# LDAQ-MOD-ENC4.net
KiCad netlist of a schematic drawn in EAGLE
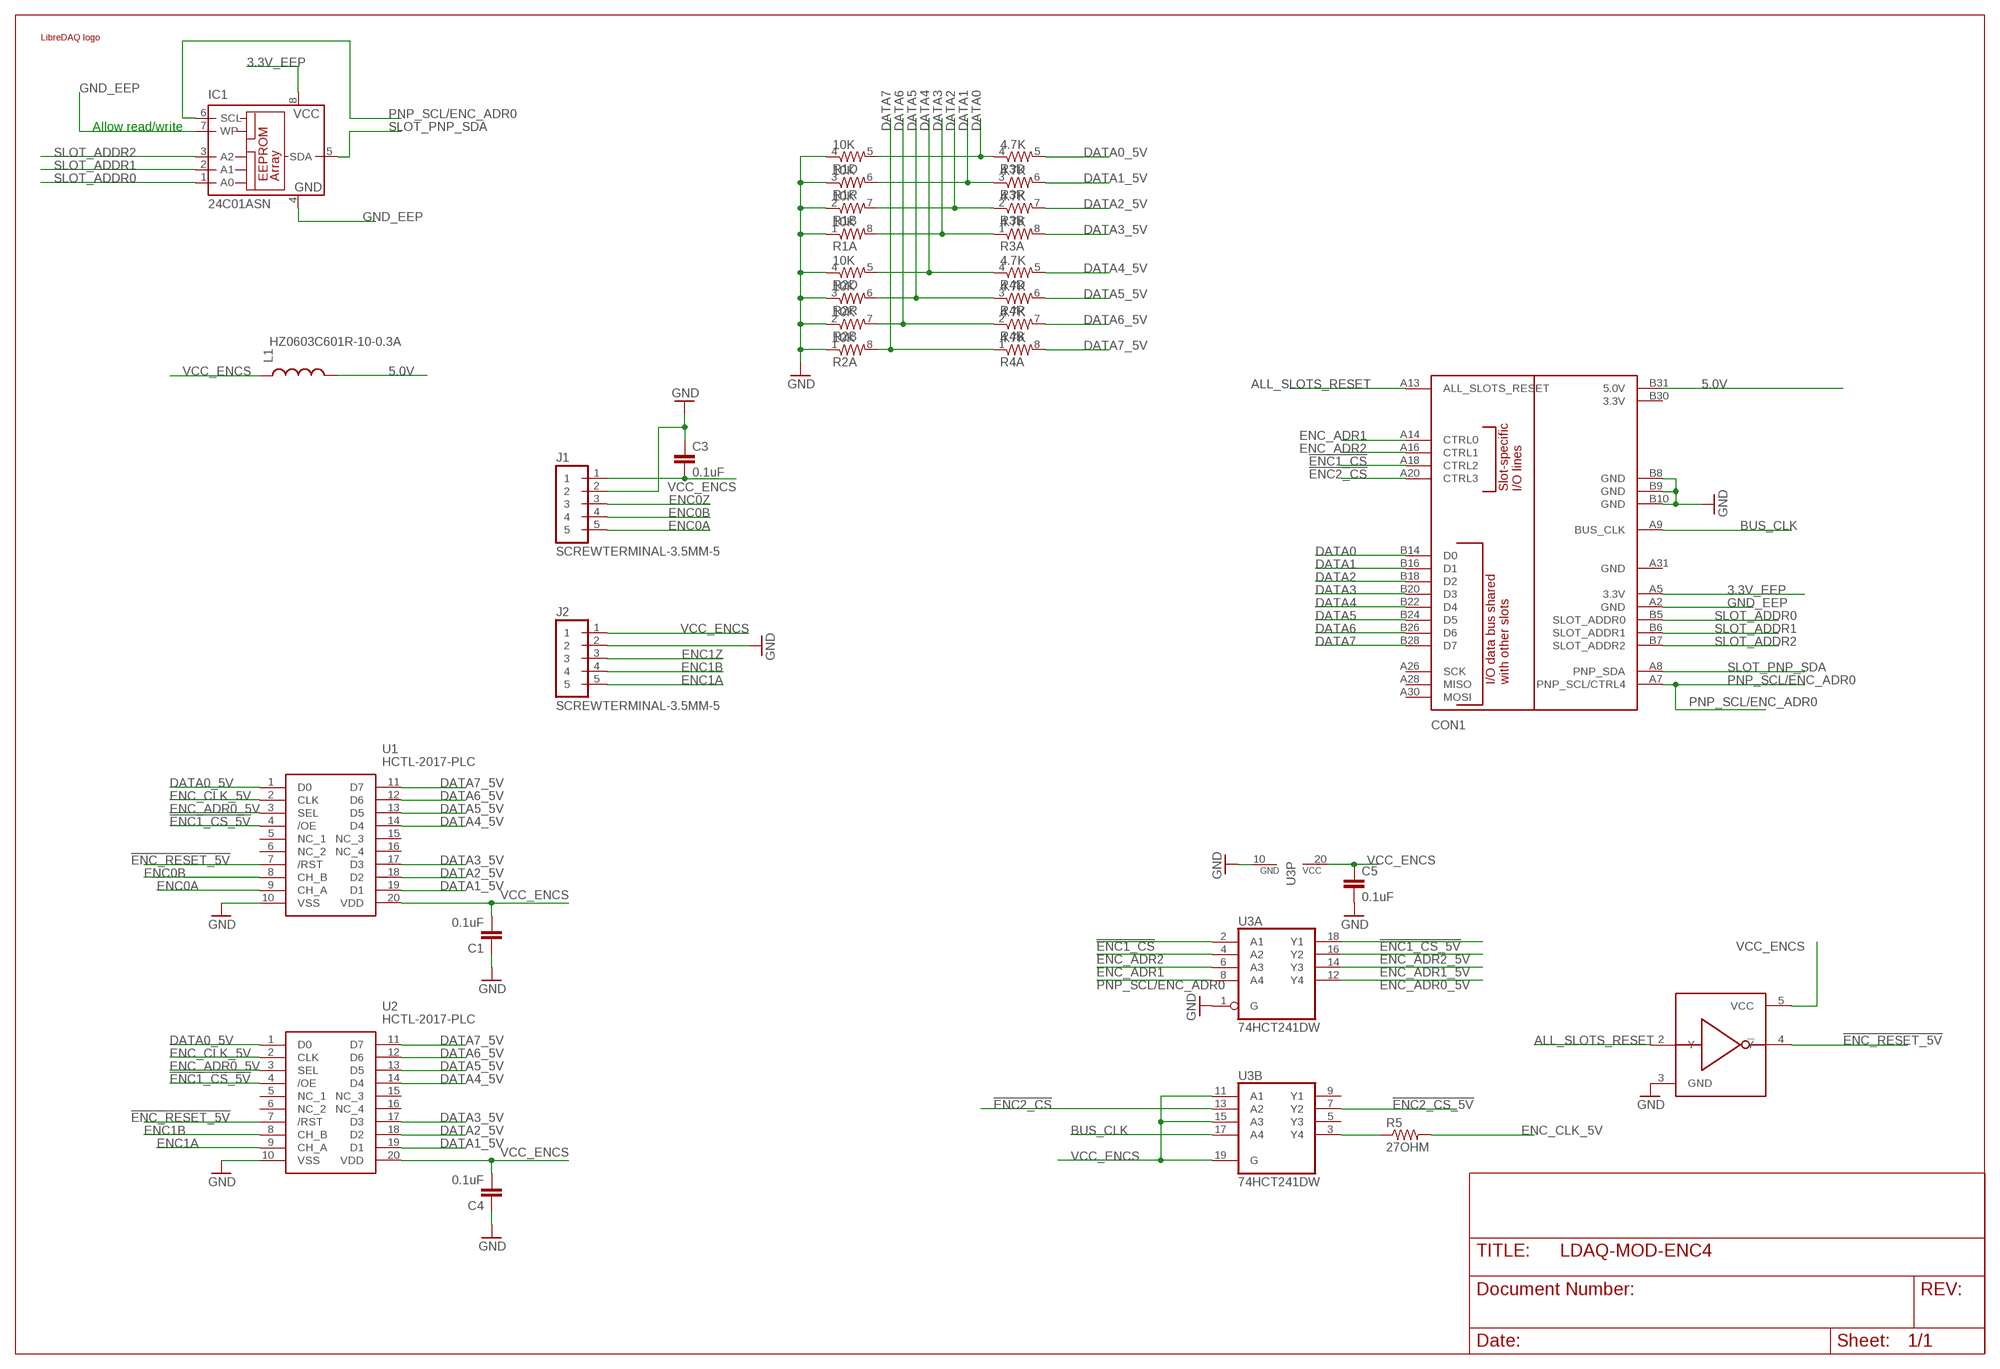
[diagram p0: schematic, sheet 1]

(export (version "E")
  (design (tool "Eeschema 10.0.6"))
  (components
    (comp (ref "C1")
      (value "0.1uF")
      (footprint "eagle-import:0603-CAP")
      (libsource (lib "eagle-import") (part "0.1UF-25V(+80/-20%)(0603)"))
    )
    (comp (ref "C3")
      (value "0.1uF")
      (footprint "eagle-import:0603-CAP")
      (libsource (lib "eagle-import") (part "0.1UF-25V(+80/-20%)(0603)"))
    )
    (comp (ref "C4")
      (value "0.1uF")
      (footprint "eagle-import:0603-CAP")
      (libsource (lib "eagle-import") (part "0.1UF-25V(+80/-20%)(0603)"))
    )
    (comp (ref "C5")
      (value "0.1uF")
      (footprint "eagle-import:0603-CAP")
      (libsource (lib "eagle-import") (part "0.1UF-25V(+80/-20%)(0603)"))
    )
    (comp (ref "CON1")
      (value "BOARD")
      (footprint "eagle-import:PCI-E_64_EDGE_70X60_PADS-ONLY")
      (libsource (lib "eagle-import") (part "LIBREDAQ_DAUGHTER_BOARDPCI-64-SIZE1-PADS"))
    )
    (comp (ref "IC1")
      (value "24C01ASN")
      (footprint "eagle-import:SO-08")
      (fields (field (name "MPN") "AT24C01BN-SH-B"))
      (libsource (lib "eagle-import") (part "24CSN01A"))
    )
    (comp (ref "J1")
      (value "SCREWTERMINAL-3.5MM-5")
      (footprint "eagle-import:SCREWTERMINAL-3.5MM-5")
      (libsource (lib "eagle-import") (part "SCREWTERMINAL-3.5MM-5"))
    )
    (comp (ref "J2")
      (value "SCREWTERMINAL-3.5MM-5")
      (footprint "eagle-import:SCREWTERMINAL-3.5MM-5")
      (libsource (lib "eagle-import") (part "SCREWTERMINAL-3.5MM-5"))
    )
    (comp (ref "L1")
      (value "HZ0603C601R-10-0.3A")
      (footprint "eagle-import:0603")
      (libsource (lib "eagle-import") (part "INDUCTOR0603"))
    )
    (comp (ref "LOGO1")
      (value "LIBREDAQ_LOGO_MINILOGO_GENERIC")
      (footprint "eagle-import:LIBREDAQ_LOGO")
      (libsource (lib "eagle-import") (part "LIBREDAQ_LOGO_MINILOGO_GENERIC"))
    )
    (comp (ref "R1")
      (value "10K")
      (footprint "eagle-import:0603-ARV")
      (libsource (lib "eagle-import") (part "RESISTOR-ARRAY0603-ARV"))
    )
    (comp (ref "R2")
      (value "10K")
      (footprint "eagle-import:0603-ARV")
      (libsource (lib "eagle-import") (part "RESISTOR-ARRAY0603-ARV"))
    )
    (comp (ref "R3")
      (value "4.7K")
      (footprint "eagle-import:0603-ARV")
      (libsource (lib "eagle-import") (part "RESISTOR-ARRAY0603-ARV"))
    )
    (comp (ref "R4")
      (value "4.7K")
      (footprint "eagle-import:0603-ARV")
      (libsource (lib "eagle-import") (part "RESISTOR-ARRAY0603-ARV"))
    )
    (comp (ref "R5")
      (value "27OHM")
      (footprint "eagle-import:0603")
      (libsource (lib "eagle-import") (part "33OHM1/10W1%(0603)"))
    )
    (comp (ref "U1")
      (value "HCTL-2017-PLC")
      (footprint "eagle-import:PLCC127P991X991X457-20N")
      (libsource (lib "eagle-import") (part "HCTL-2017-PLC"))
    )
    (comp (ref "U2")
      (value "HCTL-2017-PLC")
      (footprint "eagle-import:PLCC127P991X991X457-20N")
      (libsource (lib "eagle-import") (part "HCTL-2017-PLC"))
    )
    (comp (ref "U3")
      (value "74HCT241DW")
      (footprint "eagle-import:SO20W")
      (libsource (lib "eagle-import") (part "74241DWHCT"))
    )
    (comp (ref "U4")
      (value "74AHCT1G04")
      (footprint "eagle-import:SOT353-SC70-5")
      (libsource (lib "eagle-import") (part "74AHCT1G04"))
    )
  )
  (nets
    (net (code "1") (name "/3.3V_EEP") (class "Default")
      (node (ref "CON1") (pin "A5") (pinfunction "3.3V_A5") (pintype "bidirectional"))
      (node (ref "IC1") (pin "8") (pinfunction "VCC_8") (pintype "power_in"))
    )
    (net (code "2") (name "/5.0V") (class "Default")
      (node (ref "CON1") (pin "B31") (pinfunction "5.0V_B31") (pintype "bidirectional"))
      (node (ref "L1") (pin "2") (pinfunction "2_2") (pintype "passive"))
    )
    (net (code "3") (name "/ALL_SLOTS_RESET") (class "Default")
      (node (ref "CON1") (pin "A13") (pinfunction "ALL_SLOTS_RESET_A13") (pintype "bidirectional"))
      (node (ref "U4") (pin "2") (pinfunction "Y_2") (pintype "bidirectional"))
    )
    (net (code "4") (name "/BUS_CLK") (class "Default")
      (node (ref "CON1") (pin "A9") (pinfunction "BUS_CLK_A9") (pintype "bidirectional"))
      (node (ref "U3") (pin "17") (pinfunction "A4_17") (pintype "input"))
    )
    (net (code "5") (name "/DATA0") (class "Default")
      (node (ref "CON1") (pin "B14") (pinfunction "D0_B14") (pintype "bidirectional"))
      (node (ref "R1") (pin "5") (pinfunction "2_5") (pintype "passive"))
      (node (ref "R3") (pin "4") (pinfunction "1_4") (pintype "passive"))
    )
    (net (code "6") (name "/DATA0_5V") (class "Default")
      (node (ref "R3") (pin "5") (pinfunction "2_5") (pintype "passive"))
      (node (ref "U1") (pin "1") (pinfunction "D0_1") (pintype "output"))
      (node (ref "U2") (pin "1") (pinfunction "D0_1") (pintype "output"))
    )
    (net (code "7") (name "/DATA1") (class "Default")
      (node (ref "CON1") (pin "B16") (pinfunction "D1_B16") (pintype "bidirectional"))
      (node (ref "R1") (pin "6") (pinfunction "2_6") (pintype "passive"))
      (node (ref "R3") (pin "3") (pinfunction "1_3") (pintype "passive"))
    )
    (net (code "8") (name "/DATA1_5V") (class "Default")
      (node (ref "R3") (pin "6") (pinfunction "2_6") (pintype "passive"))
      (node (ref "U1") (pin "19") (pinfunction "D1_19") (pintype "output"))
      (node (ref "U2") (pin "19") (pinfunction "D1_19") (pintype "output"))
    )
    (net (code "9") (name "/DATA2") (class "Default")
      (node (ref "CON1") (pin "B18") (pinfunction "D2_B18") (pintype "bidirectional"))
      (node (ref "R1") (pin "7") (pinfunction "2_7") (pintype "passive"))
      (node (ref "R3") (pin "2") (pinfunction "1_2") (pintype "passive"))
    )
    (net (code "10") (name "/DATA2_5V") (class "Default")
      (node (ref "R3") (pin "7") (pinfunction "2_7") (pintype "passive"))
      (node (ref "U1") (pin "18") (pinfunction "D2_18") (pintype "output"))
      (node (ref "U2") (pin "18") (pinfunction "D2_18") (pintype "output"))
    )
    (net (code "11") (name "/DATA3") (class "Default")
      (node (ref "CON1") (pin "B20") (pinfunction "D3_B20") (pintype "bidirectional"))
      (node (ref "R1") (pin "8") (pinfunction "2_8") (pintype "passive"))
      (node (ref "R3") (pin "1") (pinfunction "1_1") (pintype "passive"))
    )
    (net (code "12") (name "/DATA3_5V") (class "Default")
      (node (ref "R3") (pin "8") (pinfunction "2_8") (pintype "passive"))
      (node (ref "U1") (pin "17") (pinfunction "D3_17") (pintype "output"))
      (node (ref "U2") (pin "17") (pinfunction "D3_17") (pintype "output"))
    )
    (net (code "13") (name "/DATA4") (class "Default")
      (node (ref "CON1") (pin "B22") (pinfunction "D4_B22") (pintype "bidirectional"))
      (node (ref "R2") (pin "5") (pinfunction "2_5") (pintype "passive"))
      (node (ref "R4") (pin "4") (pinfunction "1_4") (pintype "passive"))
    )
    (net (code "14") (name "/DATA4_5V") (class "Default")
      (node (ref "R4") (pin "5") (pinfunction "2_5") (pintype "passive"))
      (node (ref "U1") (pin "14") (pinfunction "D4_14") (pintype "output"))
      (node (ref "U2") (pin "14") (pinfunction "D4_14") (pintype "output"))
    )
    (net (code "15") (name "/DATA5") (class "Default")
      (node (ref "CON1") (pin "B24") (pinfunction "D5_B24") (pintype "bidirectional"))
      (node (ref "R2") (pin "6") (pinfunction "2_6") (pintype "passive"))
      (node (ref "R4") (pin "3") (pinfunction "1_3") (pintype "passive"))
    )
    (net (code "16") (name "/DATA5_5V") (class "Default")
      (node (ref "R4") (pin "6") (pinfunction "2_6") (pintype "passive"))
      (node (ref "U1") (pin "13") (pinfunction "D5_13") (pintype "output"))
      (node (ref "U2") (pin "13") (pinfunction "D5_13") (pintype "output"))
    )
    (net (code "17") (name "/DATA6") (class "Default")
      (node (ref "CON1") (pin "B26") (pinfunction "D6_B26") (pintype "bidirectional"))
      (node (ref "R2") (pin "7") (pinfunction "2_7") (pintype "passive"))
      (node (ref "R4") (pin "2") (pinfunction "1_2") (pintype "passive"))
    )
    (net (code "18") (name "/DATA6_5V") (class "Default")
      (node (ref "R4") (pin "7") (pinfunction "2_7") (pintype "passive"))
      (node (ref "U1") (pin "12") (pinfunction "D6_12") (pintype "output"))
      (node (ref "U2") (pin "12") (pinfunction "D6_12") (pintype "output"))
    )
    (net (code "19") (name "/DATA7") (class "Default")
      (node (ref "CON1") (pin "B28") (pinfunction "D7_B28") (pintype "bidirectional"))
      (node (ref "R2") (pin "8") (pinfunction "2_8") (pintype "passive"))
      (node (ref "R4") (pin "1") (pinfunction "1_1") (pintype "passive"))
    )
    (net (code "20") (name "/DATA7_5V") (class "Default")
      (node (ref "R4") (pin "8") (pinfunction "2_8") (pintype "passive"))
      (node (ref "U1") (pin "11") (pinfunction "D7_11") (pintype "output"))
      (node (ref "U2") (pin "11") (pinfunction "D7_11") (pintype "output"))
    )
    (net (code "21") (name "/ENC0A") (class "Default")
      (node (ref "J1") (pin "5") (pinfunction "5_5") (pintype "bidirectional"))
      (node (ref "U1") (pin "9") (pinfunction "CH_A_9") (pintype "input"))
    )
    (net (code "22") (name "/ENC0B") (class "Default")
      (node (ref "J1") (pin "4") (pinfunction "4_4") (pintype "bidirectional"))
      (node (ref "U1") (pin "8") (pinfunction "CH_B_8") (pintype "input"))
    )
    (net (code "23") (name "/ENC0Z") (class "Default")
      (node (ref "J1") (pin "3") (pinfunction "3_3") (pintype "bidirectional"))
    )
    (net (code "24") (name "/ENC1A") (class "Default")
      (node (ref "J2") (pin "5") (pinfunction "5_5") (pintype "bidirectional"))
      (node (ref "U2") (pin "9") (pinfunction "CH_A_9") (pintype "input"))
    )
    (net (code "25") (name "/ENC1B") (class "Default")
      (node (ref "J2") (pin "4") (pinfunction "4_4") (pintype "bidirectional"))
      (node (ref "U2") (pin "8") (pinfunction "CH_B_8") (pintype "input"))
    )
    (net (code "26") (name "/ENC1Z") (class "Default")
      (node (ref "J2") (pin "3") (pinfunction "3_3") (pintype "bidirectional"))
    )
    (net (code "27") (name "/ENC_ADR0_5V") (class "Default")
      (node (ref "U1") (pin "3") (pinfunction "SEL_3") (pintype "input"))
      (node (ref "U2") (pin "3") (pinfunction "SEL_3") (pintype "input"))
      (node (ref "U3") (pin "12") (pinfunction "Y4_12") (pintype "tri_state"))
    )
    (net (code "28") (name "/ENC_ADR1") (class "Default")
      (node (ref "CON1") (pin "A14") (pinfunction "CTRL0_A14") (pintype "bidirectional"))
      (node (ref "U3") (pin "6") (pinfunction "A3_6") (pintype "input"))
    )
    (net (code "29") (name "/ENC_ADR1_5V") (class "Default")
      (node (ref "U3") (pin "14") (pinfunction "Y3_14") (pintype "tri_state"))
    )
    (net (code "30") (name "/ENC_ADR2") (class "Default")
      (node (ref "CON1") (pin "A16") (pinfunction "CTRL1_A16") (pintype "bidirectional"))
      (node (ref "U3") (pin "4") (pinfunction "A2_4") (pintype "input"))
    )
    (net (code "31") (name "/ENC_ADR2_5V") (class "Default")
      (node (ref "U3") (pin "16") (pinfunction "Y2_16") (pintype "tri_state"))
    )
    (net (code "32") (name "/ENC_CLK_5V") (class "Default")
      (node (ref "R5") (pin "2") (pinfunction "2_2") (pintype "passive"))
      (node (ref "U1") (pin "2") (pinfunction "CLK_2") (pintype "input"))
      (node (ref "U2") (pin "2") (pinfunction "CLK_2") (pintype "input"))
    )
    (net (code "33") (name "/GND_EEP") (class "Default")
      (node (ref "CON1") (pin "A2") (pinfunction "GND_A2") (pintype "bidirectional"))
      (node (ref "IC1") (pin "4") (pinfunction "GND_4") (pintype "power_in"))
      (node (ref "IC1") (pin "7") (pinfunction "WP_7") (pintype "input"))
    )
    (net (code "34") (name "/PNP_SCL{slash}ENC_ADR0") (class "Default")
      (node (ref "CON1") (pin "A7") (pinfunction "PNP_SCL/CTRL4_A7") (pintype "bidirectional"))
      (node (ref "IC1") (pin "6") (pinfunction "SCL_6") (pintype "input"))
      (node (ref "U3") (pin "8") (pinfunction "A4_8") (pintype "input"))
    )
    (net (code "35") (name "/SLOT_ADDR0") (class "Default")
      (node (ref "CON1") (pin "B5") (pinfunction "SLOT_ADDR0_B5") (pintype "bidirectional"))
      (node (ref "IC1") (pin "1") (pinfunction "A0_1") (pintype "input"))
    )
    (net (code "36") (name "/SLOT_ADDR1") (class "Default")
      (node (ref "CON1") (pin "B6") (pinfunction "SLOT_ADDR1_B6") (pintype "bidirectional"))
      (node (ref "IC1") (pin "2") (pinfunction "A1_2") (pintype "input"))
    )
    (net (code "37") (name "/SLOT_ADDR2") (class "Default")
      (node (ref "CON1") (pin "B7") (pinfunction "SLOT_ADDR2_B7") (pintype "bidirectional"))
      (node (ref "IC1") (pin "3") (pinfunction "A2_3") (pintype "input"))
    )
    (net (code "38") (name "/SLOT_PNP_SDA") (class "Default")
      (node (ref "CON1") (pin "A8") (pinfunction "PNP_SDA_A8") (pintype "bidirectional"))
      (node (ref "IC1") (pin "5") (pinfunction "SDA_5") (pintype "bidirectional"))
    )
    (net (code "39") (name "/VCC_ENCS") (class "Default")
      (node (ref "C1") (pin "2") (pinfunction "2_2") (pintype "passive"))
      (node (ref "C3") (pin "2") (pinfunction "2_2") (pintype "passive"))
      (node (ref "C4") (pin "2") (pinfunction "2_2") (pintype "passive"))
      (node (ref "C5") (pin "1") (pinfunction "1_1") (pintype "passive"))
      (node (ref "J1") (pin "1") (pinfunction "1_1") (pintype "bidirectional"))
      (node (ref "J2") (pin "1") (pinfunction "1_1") (pintype "bidirectional"))
      (node (ref "L1") (pin "1") (pinfunction "1_1") (pintype "passive"))
      (node (ref "U1") (pin "20") (pinfunction "VDD_20") (pintype "power_in"))
      (node (ref "U2") (pin "20") (pinfunction "VDD_20") (pintype "power_in"))
      (node (ref "U3") (pin "11") (pinfunction "A1_11") (pintype "input"))
      (node (ref "U3") (pin "15") (pinfunction "A3_15") (pintype "input"))
      (node (ref "U3") (pin "19") (pinfunction "G_19") (pintype "input"))
      (node (ref "U3") (pin "20") (pinfunction "VCC_20") (pintype "power_in"))
      (node (ref "U4") (pin "5") (pinfunction "VCC_5") (pintype "bidirectional"))
    )
    (net (code "40") (name "/~{ENC1_CS_5V}") (class "Default")
      (node (ref "U1") (pin "4") (pinfunction "/OE_4") (pintype "input"))
      (node (ref "U2") (pin "4") (pinfunction "/OE_4") (pintype "input"))
      (node (ref "U3") (pin "18") (pinfunction "Y1_18") (pintype "tri_state"))
    )
    (net (code "41") (name "/~{ENC1_CS}") (class "Default")
      (node (ref "CON1") (pin "A18") (pinfunction "CTRL2_A18") (pintype "bidirectional"))
      (node (ref "U3") (pin "2") (pinfunction "A1_2") (pintype "input"))
    )
    (net (code "42") (name "/~{ENC2_CS_5V}") (class "Default")
      (node (ref "U3") (pin "7") (pinfunction "Y2_7") (pintype "tri_state"))
    )
    (net (code "43") (name "/~{ENC2_CS}") (class "Default")
      (node (ref "CON1") (pin "A20") (pinfunction "CTRL3_A20") (pintype "bidirectional"))
      (node (ref "U3") (pin "13") (pinfunction "A2_13") (pintype "input"))
    )
    (net (code "44") (name "/~{ENC_RESET_5V}") (class "Default")
      (node (ref "U1") (pin "7") (pinfunction "/RST_7") (pintype "input"))
      (node (ref "U2") (pin "7") (pinfunction "/RST_7") (pintype "input"))
      (node (ref "U4") (pin "4") (pinfunction "~{Y}_4") (pintype "bidirectional"))
    )
    (net (code "45") (name "GND") (class "Default")
      (node (ref "C1") (pin "1") (pinfunction "1_1") (pintype "passive"))
      (node (ref "C3") (pin "1") (pinfunction "1_1") (pintype "passive"))
      (node (ref "C4") (pin "1") (pinfunction "1_1") (pintype "passive"))
      (node (ref "C5") (pin "2") (pinfunction "2_2") (pintype "passive"))
      (node (ref "CON1") (pin "B10") (pinfunction "GND_B10") (pintype "bidirectional"))
      (node (ref "CON1") (pin "B8") (pinfunction "GND_B8") (pintype "bidirectional"))
      (node (ref "CON1") (pin "B9") (pinfunction "GND_B9") (pintype "bidirectional"))
      (node (ref "J1") (pin "2") (pinfunction "2_2") (pintype "bidirectional"))
      (node (ref "J2") (pin "2") (pinfunction "2_2") (pintype "bidirectional"))
      (node (ref "R1") (pin "1") (pinfunction "1_1") (pintype "passive"))
      (node (ref "R1") (pin "2") (pinfunction "1_2") (pintype "passive"))
      (node (ref "R1") (pin "3") (pinfunction "1_3") (pintype "passive"))
      (node (ref "R1") (pin "4") (pinfunction "1_4") (pintype "passive"))
      (node (ref "R2") (pin "1") (pinfunction "1_1") (pintype "passive"))
      (node (ref "R2") (pin "2") (pinfunction "1_2") (pintype "passive"))
      (node (ref "R2") (pin "3") (pinfunction "1_3") (pintype "passive"))
      (node (ref "R2") (pin "4") (pinfunction "1_4") (pintype "passive"))
      (node (ref "U1") (pin "10") (pinfunction "VSS_10") (pintype "power_in"))
      (node (ref "U2") (pin "10") (pinfunction "VSS_10") (pintype "power_in"))
      (node (ref "U3") (pin "1") (pinfunction "G_1") (pintype "input"))
      (node (ref "U3") (pin "10") (pinfunction "GND_10") (pintype "power_in"))
      (node (ref "U4") (pin "3") (pinfunction "GND_3") (pintype "bidirectional"))
    )
    (net (code "46") (name "Net-(U3B-Y4)") (class "Default")
      (node (ref "R5") (pin "1") (pinfunction "1_1") (pintype "passive"))
      (node (ref "U3") (pin "3") (pinfunction "Y4_3") (pintype "tri_state"))
    )
    (net (code "47") (name "unconnected-(CON1-3.3V-PadB30)") (class "Default")
      (node (ref "CON1") (pin "B30") (pinfunction "3.3V_B30") (pintype "bidirectional"))
    )
    (net (code "48") (name "unconnected-(CON1-GND-PadA31)") (class "Default")
      (node (ref "CON1") (pin "A31") (pinfunction "GND_A31") (pintype "bidirectional"))
    )
    (net (code "49") (name "unconnected-(CON1-MISO-PadA28)") (class "Default")
      (node (ref "CON1") (pin "A28") (pinfunction "MISO_A28") (pintype "bidirectional"))
    )
    (net (code "50") (name "unconnected-(CON1-MOSI-PadA30)") (class "Default")
      (node (ref "CON1") (pin "A30") (pinfunction "MOSI_A30") (pintype "bidirectional"))
    )
    (net (code "51") (name "unconnected-(CON1-SCK-PadA26)") (class "Default")
      (node (ref "CON1") (pin "A26") (pinfunction "SCK_A26") (pintype "bidirectional"))
    )
    (net (code "52") (name "unconnected-(U1-NC_1-Pad5)") (class "Default")
      (node (ref "U1") (pin "5") (pinfunction "NC_1_5") (pintype "bidirectional"))
    )
    (net (code "53") (name "unconnected-(U1-NC_2-Pad6)") (class "Default")
      (node (ref "U1") (pin "6") (pinfunction "NC_2_6") (pintype "bidirectional"))
    )
    (net (code "54") (name "unconnected-(U1-NC_3-Pad15)") (class "Default")
      (node (ref "U1") (pin "15") (pinfunction "NC_3_15") (pintype "bidirectional"))
    )
    (net (code "55") (name "unconnected-(U1-NC_4-Pad16)") (class "Default")
      (node (ref "U1") (pin "16") (pinfunction "NC_4_16") (pintype "bidirectional"))
    )
    (net (code "56") (name "unconnected-(U2-NC_1-Pad5)") (class "Default")
      (node (ref "U2") (pin "5") (pinfunction "NC_1_5") (pintype "bidirectional"))
    )
    (net (code "57") (name "unconnected-(U2-NC_2-Pad6)") (class "Default")
      (node (ref "U2") (pin "6") (pinfunction "NC_2_6") (pintype "bidirectional"))
    )
    (net (code "58") (name "unconnected-(U2-NC_3-Pad15)") (class "Default")
      (node (ref "U2") (pin "15") (pinfunction "NC_3_15") (pintype "bidirectional"))
    )
    (net (code "59") (name "unconnected-(U2-NC_4-Pad16)") (class "Default")
      (node (ref "U2") (pin "16") (pinfunction "NC_4_16") (pintype "bidirectional"))
    )
    (net (code "60") (name "unconnected-(U3B-Y1-Pad9)") (class "Default")
      (node (ref "U3") (pin "9") (pinfunction "Y1_9") (pintype "tri_state"))
    )
    (net (code "61") (name "unconnected-(U3B-Y3-Pad5)") (class "Default")
      (node (ref "U3") (pin "5") (pinfunction "Y3_5") (pintype "tri_state"))
    )
  )
)
